# SomTest1.net
KiCad netlist of a schematic drawn in EAGLE
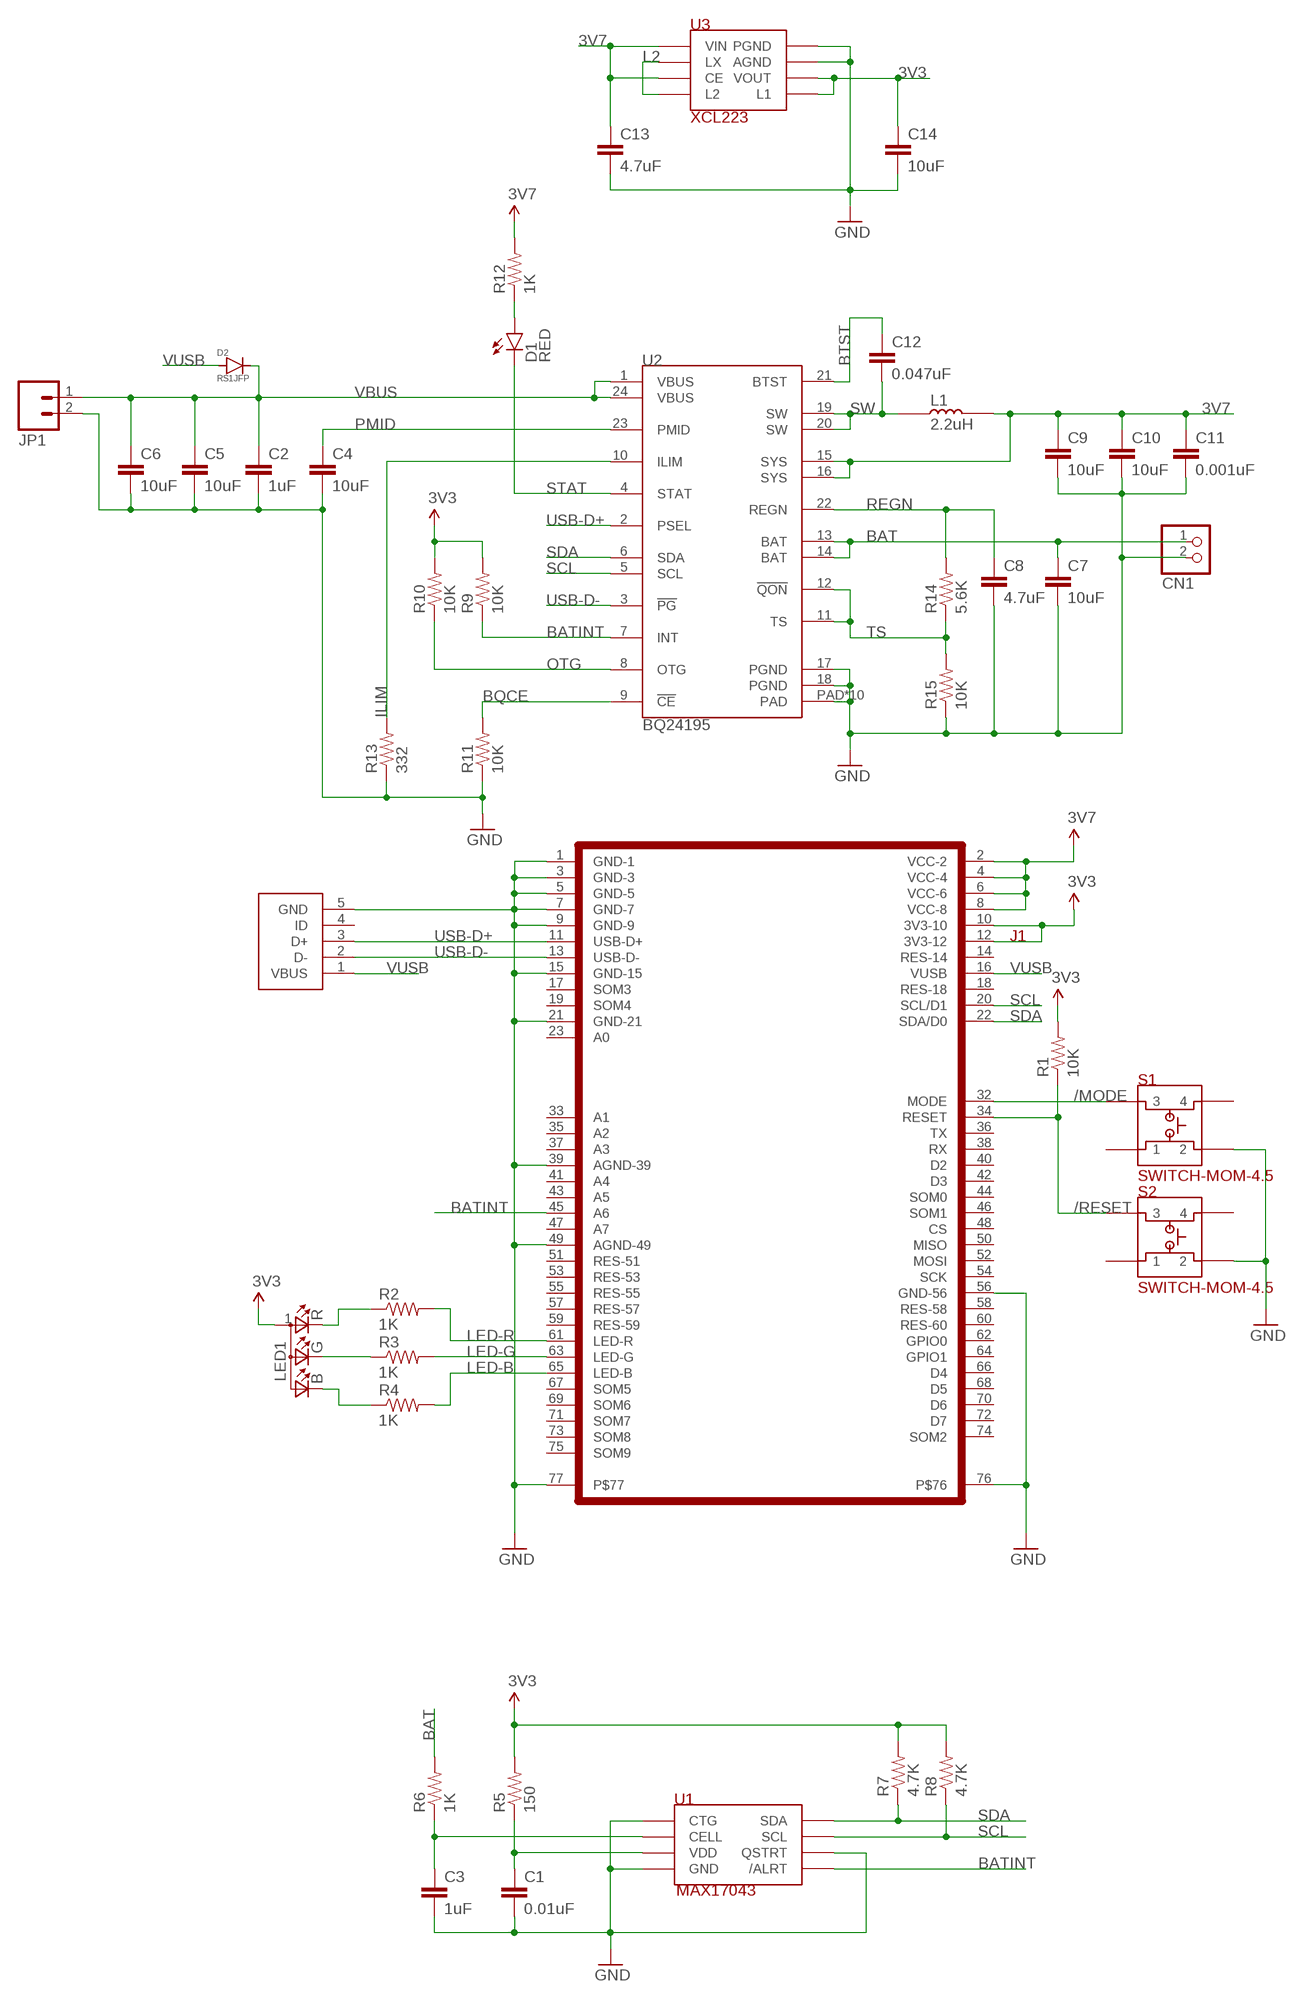
[diagram p0: schematic, sheet 1]

(export (version "E")
  (design (tool "Eeschema 10.0.6"))
  (components
    (comp (ref "C1")
      (value "0.01uF")
      (footprint "eagle-import:0603-CAP")
      (libsource (lib "eagle-import") (part "CAP-0.01UF-0603"))
    )
    (comp (ref "C2")
      (value "1uF")
      (footprint "eagle-import:0603-CAP")
      (libsource (lib "eagle-import") (part "CAP-1UF-0603.DEV"))
    )
    (comp (ref "C3")
      (value "1uF")
      (footprint "eagle-import:0603-CAP")
      (libsource (lib "eagle-import") (part "CAP-1UF-0603.DEV"))
    )
    (comp (ref "C4")
      (value "10uF")
      (footprint "eagle-import:0603-CAP")
      (libsource (lib "eagle-import") (part "CAP-10UF-0603"))
    )
    (comp (ref "C5")
      (value "10uF")
      (footprint "eagle-import:0603-CAP")
      (libsource (lib "eagle-import") (part "CAP-10UF-0603"))
    )
    (comp (ref "C6")
      (value "10uF")
      (footprint "eagle-import:0603-CAP")
      (libsource (lib "eagle-import") (part "CAP-10UF-0603"))
    )
    (comp (ref "C7")
      (value "10uF")
      (footprint "eagle-import:0603-CAP")
      (libsource (lib "eagle-import") (part "CAP-10UF-0603"))
    )
    (comp (ref "C8")
      (value "4.7uF")
      (footprint "eagle-import:0603-CAP")
      (libsource (lib "eagle-import") (part "CAP-4.7UF-0603"))
    )
    (comp (ref "C9")
      (value "10uF")
      (footprint "eagle-import:0603-CAP")
      (libsource (lib "eagle-import") (part "CAP-10UF-0603"))
    )
    (comp (ref "C10")
      (value "10uF")
      (footprint "eagle-import:0603-CAP")
      (libsource (lib "eagle-import") (part "CAP-10UF-0603"))
    )
    (comp (ref "C11")
      (value "0.001uF")
      (footprint "eagle-import:0603-CAP")
      (libsource (lib "eagle-import") (part "CAP-0.001UF-0603"))
    )
    (comp (ref "C12")
      (value "0.047uF")
      (footprint "eagle-import:0603-CAP")
      (libsource (lib "eagle-import") (part "CAP-0.047UF-0603"))
    )
    (comp (ref "C13")
      (value "4.7uF")
      (footprint "eagle-import:0603-CAP")
      (libsource (lib "eagle-import") (part "CAP-4.7UF-0603"))
    )
    (comp (ref "C14")
      (value "10uF")
      (footprint "eagle-import:0603-CAP")
      (libsource (lib "eagle-import") (part "CAP-10UF-0603"))
    )
    (comp (ref "CN1")
      (value "JST_2PIN-THM")
      (footprint "eagle-import:JST-PH-2-THM")
      (libsource (lib "eagle-import") (part "JST_2PIN-THM"))
    )
    (comp (ref "D1")
      (value "RED")
      (footprint "eagle-import:LED-0603")
      (libsource (lib "eagle-import") (part "LED-RED"))
    )
    (comp (ref "D2")
      (value "RS1JFP")
      (footprint "eagle-import:SOD-123HE-ON")
      (libsource (lib "eagle-import") (part "DIODE-RS1JFP"))
    )
    (comp (ref "J1")
      (value "SPARK_M.2EKEY")
      (footprint "eagle-import:SPARK_M.2EKEY-LESS-CREAM")
      (libsource (lib "eagle-import") (part "SPARK_M.2EKEY"))
    )
    (comp (ref "JP1")
      (value "M02PTH")
      (footprint "eagle-import:1X02")
      (libsource (lib "eagle-import") (part "M02PTH"))
    )
    (comp (ref "L1")
      (value "2.2uH")
      (footprint "eagle-import:1008-BOURNS")
      (libsource (lib "eagle-import") (part "INDUCTOR-2.2UH"))
    )
    (comp (ref "LED1")
      (value "LED-RGB-CREE-SMD")
      (footprint "eagle-import:LED-RGB-CREE-SMD")
      (libsource (lib "eagle-import") (part "LED-RGB-CREE-SMD"))
    )
    (comp (ref "R1")
      (value "10K")
      (footprint "eagle-import:0603-RES")
      (libsource (lib "eagle-import") (part "RES-10K-06030603"))
    )
    (comp (ref "R2")
      (value "1K")
      (footprint "eagle-import:0603-RES")
      (libsource (lib "eagle-import") (part "RES-1K-0603"))
    )
    (comp (ref "R3")
      (value "1K")
      (footprint "eagle-import:0603-RES")
      (libsource (lib "eagle-import") (part "RES-1K-0603"))
    )
    (comp (ref "R4")
      (value "1K")
      (footprint "eagle-import:0603-RES")
      (libsource (lib "eagle-import") (part "RES-1K-0603"))
    )
    (comp (ref "R5")
      (value "150")
      (footprint "eagle-import:0603-RES")
      (libsource (lib "eagle-import") (part "RES-150-0603"))
    )
    (comp (ref "R6")
      (value "1K")
      (footprint "eagle-import:0603-RES")
      (libsource (lib "eagle-import") (part "RES-1K-0603"))
    )
    (comp (ref "R7")
      (value "4.7K")
      (footprint "eagle-import:0603-RES")
      (libsource (lib "eagle-import") (part "RES-4.7K-0603"))
    )
    (comp (ref "R8")
      (value "4.7K")
      (footprint "eagle-import:0603-RES")
      (libsource (lib "eagle-import") (part "RES-4.7K-0603"))
    )
    (comp (ref "R9")
      (value "10K")
      (footprint "eagle-import:0603-RES")
      (libsource (lib "eagle-import") (part "RES-10K-06030603"))
    )
    (comp (ref "R10")
      (value "10K")
      (footprint "eagle-import:0603-RES")
      (libsource (lib "eagle-import") (part "RES-10K-06030603"))
    )
    (comp (ref "R11")
      (value "10K")
      (footprint "eagle-import:0603-RES")
      (libsource (lib "eagle-import") (part "RES-10K-06030603"))
    )
    (comp (ref "R12")
      (value "1K")
      (footprint "eagle-import:0603-RES")
      (libsource (lib "eagle-import") (part "RES-1K-0603"))
    )
    (comp (ref "R13")
      (value "332")
      (footprint "eagle-import:0603-RES")
      (libsource (lib "eagle-import") (part "RES-332-0603.DEV"))
    )
    (comp (ref "R14")
      (value "5.6K")
      (footprint "eagle-import:0603-RES")
      (libsource (lib "eagle-import") (part "RES-5.6K-0603"))
    )
    (comp (ref "R15")
      (value "10K")
      (footprint "eagle-import:0603-RES")
      (libsource (lib "eagle-import") (part "RES-10K-06030603"))
    )
    (comp (ref "S1")
      (value "SWITCH-MOM-4.5")
      (footprint "eagle-import:SWITCH-MOM-4.5")
      (libsource (lib "eagle-import") (part "SWITCH-MOM-4.5"))
    )
    (comp (ref "S2")
      (value "SWITCH-MOM-4.5")
      (footprint "eagle-import:SWITCH-MOM-4.5")
      (libsource (lib "eagle-import") (part "SWITCH-MOM-4.5"))
    )
    (comp (ref "U$3")
      (value "USB-MICRO-B-SOCKET-AMPHENOL")
      (footprint "eagle-import:USB-B-SMT-AMPHENOL")
      (libsource (lib "eagle-import") (part "USB-MICRO-B-SOCKET-AMPHENOL"))
    )
    (comp (ref "U1")
      (value "MAX17043")
      (footprint "eagle-import:9UCSP-MAXIM")
      (libsource (lib "eagle-import") (part "MAX17043"))
    )
    (comp (ref "U2")
      (value "BQ24195")
      (footprint "eagle-import:24VFQN-TI")
      (libsource (lib "eagle-import") (part "BQ24195"))
    )
    (comp (ref "U3")
      (value "XCL223")
      (footprint "eagle-import:REG-XCL223-LESS-CREAM")
      (libsource (lib "eagle-import") (part "REG-XCL223"))
    )
  )
  (nets
    (net (code "1") (name "/BAT") (class "Default")
      (node (ref "C7") (pin "1") (pinfunction "1_1") (pintype "passive"))
      (node (ref "CN1") (pin "1") (pinfunction "2_1") (pintype "passive"))
      (node (ref "R6") (pin "2") (pinfunction "2_2") (pintype "passive"))
      (node (ref "U2") (pin "13") (pinfunction "BAT_13") (pintype "passive"))
      (node (ref "U2") (pin "14") (pinfunction "BAT_14") (pintype "power_in"))
    )
    (net (code "2") (name "/BATINT") (class "Default")
      (node (ref "J1") (pin "45") (pinfunction "A6_45") (pintype "bidirectional"))
      (node (ref "R9") (pin "1") (pinfunction "1_1") (pintype "passive"))
      (node (ref "U1") (pin "C1") (pinfunction "/ALRT_C1") (pintype "output"))
      (node (ref "U2") (pin "7") (pinfunction "INT_7") (pintype "bidirectional"))
    )
    (net (code "3") (name "/BQCE") (class "Default")
      (node (ref "R11") (pin "2") (pinfunction "2_2") (pintype "passive"))
      (node (ref "U2") (pin "9") (pinfunction "~{CE}_9") (pintype "output"))
    )
    (net (code "4") (name "/BTST") (class "Default")
      (node (ref "C12") (pin "1") (pinfunction "1_1") (pintype "passive"))
      (node (ref "U2") (pin "21") (pinfunction "BTST_21") (pintype "bidirectional"))
    )
    (net (code "5") (name "/ILIM") (class "Default")
      (node (ref "R13") (pin "2") (pinfunction "2_2") (pintype "passive"))
      (node (ref "U2") (pin "10") (pinfunction "ILIM_10") (pintype "output"))
    )
    (net (code "6") (name "/L2") (class "Default")
      (node (ref "U3") (pin "5") (pinfunction "LX_5") (pintype "passive"))
      (node (ref "U3") (pin "8") (pinfunction "L2_8") (pintype "passive"))
    )
    (net (code "7") (name "/LED-B") (class "Default")
      (node (ref "J1") (pin "65") (pinfunction "LED-B_65") (pintype "bidirectional"))
      (node (ref "R4") (pin "2") (pinfunction "2_2") (pintype "passive"))
    )
    (net (code "8") (name "/LED-G") (class "Default")
      (node (ref "J1") (pin "63") (pinfunction "LED-G_63") (pintype "bidirectional"))
      (node (ref "R3") (pin "2") (pinfunction "2_2") (pintype "passive"))
    )
    (net (code "9") (name "/LED-R") (class "Default")
      (node (ref "J1") (pin "61") (pinfunction "LED-R_61") (pintype "bidirectional"))
      (node (ref "R2") (pin "2") (pinfunction "2_2") (pintype "passive"))
    )
    (net (code "10") (name "/OTG") (class "Default")
      (node (ref "R10") (pin "1") (pinfunction "1_1") (pintype "passive"))
      (node (ref "U2") (pin "8") (pinfunction "OTG_8") (pintype "bidirectional"))
    )
    (net (code "11") (name "/PMID") (class "Default")
      (node (ref "C4") (pin "1") (pinfunction "1_1") (pintype "passive"))
      (node (ref "U2") (pin "23") (pinfunction "PMID_23") (pintype "passive"))
    )
    (net (code "12") (name "/REGN") (class "Default")
      (node (ref "C8") (pin "1") (pinfunction "1_1") (pintype "passive"))
      (node (ref "R14") (pin "2") (pinfunction "2_2") (pintype "passive"))
      (node (ref "U2") (pin "22") (pinfunction "REGN_22") (pintype "bidirectional"))
    )
    (net (code "13") (name "/SCL") (class "Default")
      (node (ref "J1") (pin "20") (pinfunction "SCL/D1_20") (pintype "bidirectional"))
      (node (ref "R8") (pin "1") (pinfunction "1_1") (pintype "passive"))
      (node (ref "U1") (pin "A2") (pinfunction "SCL_A2") (pintype "bidirectional"))
      (node (ref "U2") (pin "5") (pinfunction "SCL_5") (pintype "output"))
    )
    (net (code "14") (name "/SDA") (class "Default")
      (node (ref "J1") (pin "22") (pinfunction "SDA/D0_22") (pintype "bidirectional"))
      (node (ref "R7") (pin "1") (pinfunction "1_1") (pintype "passive"))
      (node (ref "U1") (pin "A1") (pinfunction "SDA_A1") (pintype "bidirectional"))
      (node (ref "U2") (pin "6") (pinfunction "SDA_6") (pintype "bidirectional"))
    )
    (net (code "15") (name "/STAT") (class "Default")
      (node (ref "D1") (pin "C") (pinfunction "C_C") (pintype "passive"))
      (node (ref "U2") (pin "4") (pinfunction "STAT_4") (pintype "bidirectional"))
    )
    (net (code "16") (name "/SW") (class "Default")
      (node (ref "C12") (pin "2") (pinfunction "2_2") (pintype "passive"))
      (node (ref "L1") (pin "1") (pinfunction "P$1_1") (pintype "passive"))
      (node (ref "U2") (pin "19") (pinfunction "SW_19") (pintype "power_in"))
      (node (ref "U2") (pin "20") (pinfunction "SW_20") (pintype "power_in"))
    )
    (net (code "17") (name "/TS") (class "Default")
      (node (ref "R14") (pin "1") (pinfunction "1_1") (pintype "passive"))
      (node (ref "R15") (pin "2") (pinfunction "2_2") (pintype "passive"))
      (node (ref "U2") (pin "11") (pinfunction "TS_11") (pintype "bidirectional"))
      (node (ref "U2") (pin "12") (pinfunction "~{QON}_12") (pintype "bidirectional"))
    )
    (net (code "18") (name "/USB-D+") (class "Default")
      (node (ref "J1") (pin "11") (pinfunction "USB-D+_11") (pintype "bidirectional"))
      (node (ref "U$3") (pin "3") (pinfunction "D+_3") (pintype "passive"))
      (node (ref "U2") (pin "2") (pinfunction "PSEL_2") (pintype "output"))
    )
    (net (code "19") (name "/USB-D-") (class "Default")
      (node (ref "J1") (pin "13") (pinfunction "USB-D-_13") (pintype "bidirectional"))
      (node (ref "U$3") (pin "2") (pinfunction "D-_2") (pintype "passive"))
      (node (ref "U2") (pin "3") (pinfunction "~{PG}_3") (pintype "output"))
    )
    (net (code "20") (name "/VBUS") (class "Default")
      (node (ref "C2") (pin "1") (pinfunction "1_1") (pintype "passive"))
      (node (ref "C5") (pin "1") (pinfunction "1_1") (pintype "passive"))
      (node (ref "C6") (pin "1") (pinfunction "1_1") (pintype "passive"))
      (node (ref "D2") (pin "1") (pinfunction "CATHODE_1") (pintype "bidirectional"))
      (node (ref "JP1") (pin "1") (pinfunction "1_1") (pintype "passive"))
      (node (ref "U2") (pin "1") (pinfunction "VBUS_1") (pintype "power_in"))
      (node (ref "U2") (pin "24") (pinfunction "VBUS_24") (pintype "passive"))
    )
    (net (code "21") (name "/VUSB") (class "Default")
      (node (ref "D2") (pin "2") (pinfunction "ANODE_2") (pintype "bidirectional"))
      (node (ref "J1") (pin "16") (pinfunction "VUSB_16") (pintype "bidirectional"))
      (node (ref "U$3") (pin "1") (pinfunction "VBUS_1") (pintype "passive"))
    )
    (net (code "22") (name "/{slash}MODE") (class "Default")
      (node (ref "J1") (pin "32") (pinfunction "MODE_32") (pintype "bidirectional"))
      (node (ref "S1") (pin "3") (pinfunction "3_3") (pintype "passive"))
    )
    (net (code "23") (name "/{slash}RESET") (class "Default")
      (node (ref "J1") (pin "34") (pinfunction "RESET_34") (pintype "bidirectional"))
      (node (ref "R1") (pin "1") (pinfunction "1_1") (pintype "passive"))
      (node (ref "S2") (pin "3") (pinfunction "3_3") (pintype "passive"))
    )
    (net (code "24") (name "3V3") (class "Default")
      (node (ref "C14") (pin "1") (pinfunction "1_1") (pintype "passive"))
      (node (ref "J1") (pin "10") (pinfunction "3V3-10_10") (pintype "bidirectional"))
      (node (ref "J1") (pin "12") (pinfunction "3V3-12_12") (pintype "bidirectional"))
      (node (ref "LED1") (pin "1") (pinfunction "A_1") (pintype "passive"))
      (node (ref "R1") (pin "2") (pinfunction "2_2") (pintype "passive"))
      (node (ref "R10") (pin "2") (pinfunction "2_2") (pintype "passive"))
      (node (ref "R5") (pin "2") (pinfunction "2_2") (pintype "passive"))
      (node (ref "R7") (pin "2") (pinfunction "2_2") (pintype "passive"))
      (node (ref "R8") (pin "2") (pinfunction "2_2") (pintype "passive"))
      (node (ref "R9") (pin "2") (pinfunction "2_2") (pintype "passive"))
      (node (ref "U3") (pin "3") (pinfunction "VOUT_3") (pintype "passive"))
      (node (ref "U3") (pin "7") (pinfunction "L1_7") (pintype "passive"))
    )
    (net (code "25") (name "3V7") (class "Default")
      (node (ref "C10") (pin "1") (pinfunction "1_1") (pintype "passive"))
      (node (ref "C11") (pin "1") (pinfunction "1_1") (pintype "passive"))
      (node (ref "C13") (pin "1") (pinfunction "1_1") (pintype "passive"))
      (node (ref "C9") (pin "1") (pinfunction "1_1") (pintype "passive"))
      (node (ref "J1") (pin "2") (pinfunction "VCC-2_2") (pintype "bidirectional"))
      (node (ref "J1") (pin "4") (pinfunction "VCC-4_4") (pintype "bidirectional"))
      (node (ref "J1") (pin "6") (pinfunction "VCC-6_6") (pintype "bidirectional"))
      (node (ref "J1") (pin "8") (pinfunction "VCC-8_8") (pintype "bidirectional"))
      (node (ref "L1") (pin "2") (pinfunction "P$2_2") (pintype "passive"))
      (node (ref "R12") (pin "2") (pinfunction "2_2") (pintype "passive"))
      (node (ref "U2") (pin "15") (pinfunction "SYS_15") (pintype "power_in"))
      (node (ref "U2") (pin "16") (pinfunction "SYS_16") (pintype "power_in"))
      (node (ref "U3") (pin "4") (pinfunction "CE_4") (pintype "input"))
      (node (ref "U3") (pin "6") (pinfunction "VIN_6") (pintype "power_in"))
    )
    (net (code "26") (name "GND") (class "Default")
      (node (ref "C1") (pin "2") (pinfunction "2_2") (pintype "passive"))
      (node (ref "C10") (pin "2") (pinfunction "2_2") (pintype "passive"))
      (node (ref "C11") (pin "2") (pinfunction "2_2") (pintype "passive"))
      (node (ref "C13") (pin "2") (pinfunction "2_2") (pintype "passive"))
      (node (ref "C14") (pin "2") (pinfunction "2_2") (pintype "passive"))
      (node (ref "C2") (pin "2") (pinfunction "2_2") (pintype "passive"))
      (node (ref "C3") (pin "2") (pinfunction "2_2") (pintype "passive"))
      (node (ref "C4") (pin "2") (pinfunction "2_2") (pintype "passive"))
      (node (ref "C5") (pin "2") (pinfunction "2_2") (pintype "passive"))
      (node (ref "C6") (pin "2") (pinfunction "2_2") (pintype "passive"))
      (node (ref "C7") (pin "2") (pinfunction "2_2") (pintype "passive"))
      (node (ref "C8") (pin "2") (pinfunction "2_2") (pintype "passive"))
      (node (ref "C9") (pin "2") (pinfunction "2_2") (pintype "passive"))
      (node (ref "CN1") (pin "2") (pinfunction "1_2") (pintype "passive"))
      (node (ref "J1") (pin "1") (pinfunction "GND-1_1") (pintype "bidirectional"))
      (node (ref "J1") (pin "15") (pinfunction "GND-15_15") (pintype "bidirectional"))
      (node (ref "J1") (pin "21") (pinfunction "GND-21_21") (pintype "bidirectional"))
      (node (ref "J1") (pin "3") (pinfunction "GND-3_3") (pintype "bidirectional"))
      (node (ref "J1") (pin "39") (pinfunction "AGND-39_39") (pintype "bidirectional"))
      (node (ref "J1") (pin "49") (pinfunction "AGND-49_49") (pintype "bidirectional"))
      (node (ref "J1") (pin "5") (pinfunction "GND-5_5") (pintype "bidirectional"))
      (node (ref "J1") (pin "56") (pinfunction "GND-56_56") (pintype "bidirectional"))
      (node (ref "J1") (pin "7") (pinfunction "GND-7_7") (pintype "bidirectional"))
      (node (ref "J1") (pin "76") (pinfunction "P$76_76") (pintype "power_in"))
      (node (ref "J1") (pin "77") (pinfunction "P$77_77") (pintype "power_in"))
      (node (ref "J1") (pin "9") (pinfunction "GND-9_9") (pintype "bidirectional"))
      (node (ref "JP1") (pin "2") (pinfunction "2_2") (pintype "passive"))
      (node (ref "R11") (pin "1") (pinfunction "1_1") (pintype "passive"))
      (node (ref "R13") (pin "1") (pinfunction "1_1") (pintype "passive"))
      (node (ref "R15") (pin "1") (pinfunction "1_1") (pintype "passive"))
      (node (ref "S1") (pin "2") (pinfunction "2_2") (pintype "passive"))
      (node (ref "S2") (pin "2") (pinfunction "2_2") (pintype "passive"))
      (node (ref "U$3") (pin "5") (pinfunction "GND_5") (pintype "passive"))
      (node (ref "U1") (pin "A3") (pinfunction "CTG_A3") (pintype "power_in"))
      (node (ref "U1") (pin "B1") (pinfunction "QSTRT_B1") (pintype "input"))
      (node (ref "U1") (pin "C3") (pinfunction "GND_C3") (pintype "power_in"))
      (node (ref "U2") (pin "17") (pinfunction "PGND_17") (pintype "passive"))
      (node (ref "U2") (pin "18") (pinfunction "PGND_18") (pintype "passive"))
      (node (ref "U2") (pin "PAD") (pinfunction "PAD_PAD") (pintype "power_in"))
      (node (ref "U2") (pin "PAD@1") (pinfunction "PAD_PAD@1") (pintype "power_in"))
      (node (ref "U2") (pin "PAD@2") (pinfunction "PAD_PAD@2") (pintype "power_in"))
      (node (ref "U2") (pin "PAD@3") (pinfunction "PAD_PAD@3") (pintype "power_in"))
      (node (ref "U2") (pin "PAD@4") (pinfunction "PAD_PAD@4") (pintype "power_in"))
      (node (ref "U2") (pin "PAD@5") (pinfunction "PAD_PAD@5") (pintype "power_in"))
      (node (ref "U2") (pin "PAD@6") (pinfunction "PAD_PAD@6") (pintype "power_in"))
      (node (ref "U2") (pin "PAD@7") (pinfunction "PAD_PAD@7") (pintype "power_in"))
      (node (ref "U2") (pin "PAD@8") (pinfunction "PAD_PAD@8") (pintype "power_in"))
      (node (ref "U2") (pin "PAD@9") (pinfunction "PAD_PAD@9") (pintype "power_in"))
      (node (ref "U3") (pin "1") (pinfunction "PGND_1") (pintype "passive"))
      (node (ref "U3") (pin "2") (pinfunction "AGND_2") (pintype "passive"))
    )
    (net (code "27") (name "Net-(D1-PadA)") (class "Default")
      (node (ref "D1") (pin "A") (pinfunction "A_A") (pintype "passive"))
      (node (ref "R12") (pin "1") (pinfunction "1_1") (pintype "passive"))
    )
    (net (code "28") (name "Net-(LED1-B)") (class "Default")
      (node (ref "LED1") (pin "2") (pinfunction "B_2") (pintype "passive"))
      (node (ref "R4") (pin "1") (pinfunction "1_1") (pintype "passive"))
    )
    (net (code "29") (name "Net-(LED1-G)") (class "Default")
      (node (ref "LED1") (pin "3") (pinfunction "G_3") (pintype "passive"))
      (node (ref "R3") (pin "1") (pinfunction "1_1") (pintype "passive"))
    )
    (net (code "30") (name "Net-(LED1-R)") (class "Default")
      (node (ref "LED1") (pin "4") (pinfunction "R_4") (pintype "passive"))
      (node (ref "R2") (pin "1") (pinfunction "1_1") (pintype "passive"))
    )
    (net (code "31") (name "Net-(U1-CELL)") (class "Default")
      (node (ref "C3") (pin "1") (pinfunction "1_1") (pintype "passive"))
      (node (ref "R6") (pin "1") (pinfunction "1_1") (pintype "passive"))
      (node (ref "U1") (pin "B3") (pinfunction "CELL_B3") (pintype "power_in"))
    )
    (net (code "32") (name "Net-(U1-VDD)") (class "Default")
      (node (ref "C1") (pin "1") (pinfunction "1_1") (pintype "passive"))
      (node (ref "R5") (pin "1") (pinfunction "1_1") (pintype "passive"))
      (node (ref "U1") (pin "C2") (pinfunction "VDD_C2") (pintype "power_in"))
    )
    (net (code "33") (name "unconnected-(J1-A0-Pad23)") (class "Default")
      (node (ref "J1") (pin "23") (pinfunction "A0_23") (pintype "bidirectional"))
    )
    (net (code "34") (name "unconnected-(J1-A1-Pad33)") (class "Default")
      (node (ref "J1") (pin "33") (pinfunction "A1_33") (pintype "bidirectional"))
    )
    (net (code "35") (name "unconnected-(J1-A2-Pad35)") (class "Default")
      (node (ref "J1") (pin "35") (pinfunction "A2_35") (pintype "bidirectional"))
    )
    (net (code "36") (name "unconnected-(J1-A3-Pad37)") (class "Default")
      (node (ref "J1") (pin "37") (pinfunction "A3_37") (pintype "bidirectional"))
    )
    (net (code "37") (name "unconnected-(J1-A4-Pad41)") (class "Default")
      (node (ref "J1") (pin "41") (pinfunction "A4_41") (pintype "bidirectional"))
    )
    (net (code "38") (name "unconnected-(J1-A5-Pad43)") (class "Default")
      (node (ref "J1") (pin "43") (pinfunction "A5_43") (pintype "bidirectional"))
    )
    (net (code "39") (name "unconnected-(J1-A7-Pad47)") (class "Default")
      (node (ref "J1") (pin "47") (pinfunction "A7_47") (pintype "bidirectional"))
    )
    (net (code "40") (name "unconnected-(J1-CS-Pad48)") (class "Default")
      (node (ref "J1") (pin "48") (pinfunction "CS_48") (pintype "bidirectional"))
    )
    (net (code "41") (name "unconnected-(J1-D2-Pad40)") (class "Default")
      (node (ref "J1") (pin "40") (pinfunction "D2_40") (pintype "bidirectional"))
    )
    (net (code "42") (name "unconnected-(J1-D3-Pad42)") (class "Default")
      (node (ref "J1") (pin "42") (pinfunction "D3_42") (pintype "bidirectional"))
    )
    (net (code "43") (name "unconnected-(J1-D4-Pad66)") (class "Default")
      (node (ref "J1") (pin "66") (pinfunction "D4_66") (pintype "bidirectional"))
    )
    (net (code "44") (name "unconnected-(J1-D5-Pad68)") (class "Default")
      (node (ref "J1") (pin "68") (pinfunction "D5_68") (pintype "bidirectional"))
    )
    (net (code "45") (name "unconnected-(J1-D6-Pad70)") (class "Default")
      (node (ref "J1") (pin "70") (pinfunction "D6_70") (pintype "bidirectional"))
    )
    (net (code "46") (name "unconnected-(J1-D7-Pad72)") (class "Default")
      (node (ref "J1") (pin "72") (pinfunction "D7_72") (pintype "bidirectional"))
    )
    (net (code "47") (name "unconnected-(J1-GPIO0-Pad62)") (class "Default")
      (node (ref "J1") (pin "62") (pinfunction "GPIO0_62") (pintype "bidirectional"))
    )
    (net (code "48") (name "unconnected-(J1-GPIO1-Pad64)") (class "Default")
      (node (ref "J1") (pin "64") (pinfunction "GPIO1_64") (pintype "bidirectional"))
    )
    (net (code "49") (name "unconnected-(J1-MISO-Pad50)") (class "Default")
      (node (ref "J1") (pin "50") (pinfunction "MISO_50") (pintype "bidirectional"))
    )
    (net (code "50") (name "unconnected-(J1-MOSI-Pad52)") (class "Default")
      (node (ref "J1") (pin "52") (pinfunction "MOSI_52") (pintype "bidirectional"))
    )
    (net (code "51") (name "unconnected-(J1-RES-14-Pad14)") (class "Default")
      (node (ref "J1") (pin "14") (pinfunction "RES-14_14") (pintype "bidirectional"))
    )
    (net (code "52") (name "unconnected-(J1-RES-18-Pad18)") (class "Default")
      (node (ref "J1") (pin "18") (pinfunction "RES-18_18") (pintype "bidirectional"))
    )
    (net (code "53") (name "unconnected-(J1-RES-51-Pad51)") (class "Default")
      (node (ref "J1") (pin "51") (pinfunction "RES-51_51") (pintype "bidirectional"))
    )
    (net (code "54") (name "unconnected-(J1-RES-53-Pad53)") (class "Default")
      (node (ref "J1") (pin "53") (pinfunction "RES-53_53") (pintype "bidirectional"))
    )
    (net (code "55") (name "unconnected-(J1-RES-55-Pad55)") (class "Default")
      (node (ref "J1") (pin "55") (pinfunction "RES-55_55") (pintype "bidirectional"))
    )
    (net (code "56") (name "unconnected-(J1-RES-57-Pad57)") (class "Default")
      (node (ref "J1") (pin "57") (pinfunction "RES-57_57") (pintype "bidirectional"))
    )
    (net (code "57") (name "unconnected-(J1-RES-58-Pad58)") (class "Default")
      (node (ref "J1") (pin "58") (pinfunction "RES-58_58") (pintype "bidirectional"))
    )
    (net (code "58") (name "unconnected-(J1-RES-59-Pad59)") (class "Default")
      (node (ref "J1") (pin "59") (pinfunction "RES-59_59") (pintype "bidirectional"))
    )
    (net (code "59") (name "unconnected-(J1-RES-60-Pad60)") (class "Default")
      (node (ref "J1") (pin "60") (pinfunction "RES-60_60") (pintype "bidirectional"))
    )
    (net (code "60") (name "unconnected-(J1-RX-Pad38)") (class "Default")
      (node (ref "J1") (pin "38") (pinfunction "RX_38") (pintype "bidirectional"))
    )
    (net (code "61") (name "unconnected-(J1-SCK-Pad54)") (class "Default")
      (node (ref "J1") (pin "54") (pinfunction "SCK_54") (pintype "bidirectional"))
    )
    (net (code "62") (name "unconnected-(J1-SOM0-Pad44)") (class "Default")
      (node (ref "J1") (pin "44") (pinfunction "SOM0_44") (pintype "bidirectional"))
    )
    (net (code "63") (name "unconnected-(J1-SOM1-Pad46)") (class "Default")
      (node (ref "J1") (pin "46") (pinfunction "SOM1_46") (pintype "bidirectional"))
    )
    (net (code "64") (name "unconnected-(J1-SOM2-Pad74)") (class "Default")
      (node (ref "J1") (pin "74") (pinfunction "SOM2_74") (pintype "bidirectional"))
    )
    (net (code "65") (name "unconnected-(J1-SOM3-Pad17)") (class "Default")
      (node (ref "J1") (pin "17") (pinfunction "SOM3_17") (pintype "bidirectional"))
    )
    (net (code "66") (name "unconnected-(J1-SOM4-Pad19)") (class "Default")
      (node (ref "J1") (pin "19") (pinfunction "SOM4_19") (pintype "bidirectional"))
    )
    (net (code "67") (name "unconnected-(J1-SOM5-Pad67)") (class "Default")
      (node (ref "J1") (pin "67") (pinfunction "SOM5_67") (pintype "bidirectional"))
    )
    (net (code "68") (name "unconnected-(J1-SOM6-Pad69)") (class "Default")
      (node (ref "J1") (pin "69") (pinfunction "SOM6_69") (pintype "bidirectional"))
    )
    (net (code "69") (name "unconnected-(J1-SOM7-Pad71)") (class "Default")
      (node (ref "J1") (pin "71") (pinfunction "SOM7_71") (pintype "bidirectional"))
    )
    (net (code "70") (name "unconnected-(J1-SOM8-Pad73)") (class "Default")
      (node (ref "J1") (pin "73") (pinfunction "SOM8_73") (pintype "bidirectional"))
    )
    (net (code "71") (name "unconnected-(J1-SOM9-Pad75)") (class "Default")
      (node (ref "J1") (pin "75") (pinfunction "SOM9_75") (pintype "bidirectional"))
    )
    (net (code "72") (name "unconnected-(J1-TX-Pad36)") (class "Default")
      (node (ref "J1") (pin "36") (pinfunction "TX_36") (pintype "bidirectional"))
    )
    (net (code "73") (name "unconnected-(S1-Pad1)") (class "Default")
      (node (ref "S1") (pin "1") (pinfunction "1_1") (pintype "passive"))
    )
    (net (code "74") (name "unconnected-(S1-Pad4)") (class "Default")
      (node (ref "S1") (pin "4") (pinfunction "4_4") (pintype "passive"))
    )
    (net (code "75") (name "unconnected-(S2-Pad1)") (class "Default")
      (node (ref "S2") (pin "1") (pinfunction "1_1") (pintype "passive"))
    )
    (net (code "76") (name "unconnected-(S2-Pad4)") (class "Default")
      (node (ref "S2") (pin "4") (pinfunction "4_4") (pintype "passive"))
    )
    (net (code "77") (name "unconnected-(U$3-ID-Pad4)") (class "Default")
      (node (ref "U$3") (pin "4") (pinfunction "ID_4") (pintype "passive"))
    )
  )
)
